# armboard.net
KiCad netlist of a schematic drawn in EAGLE
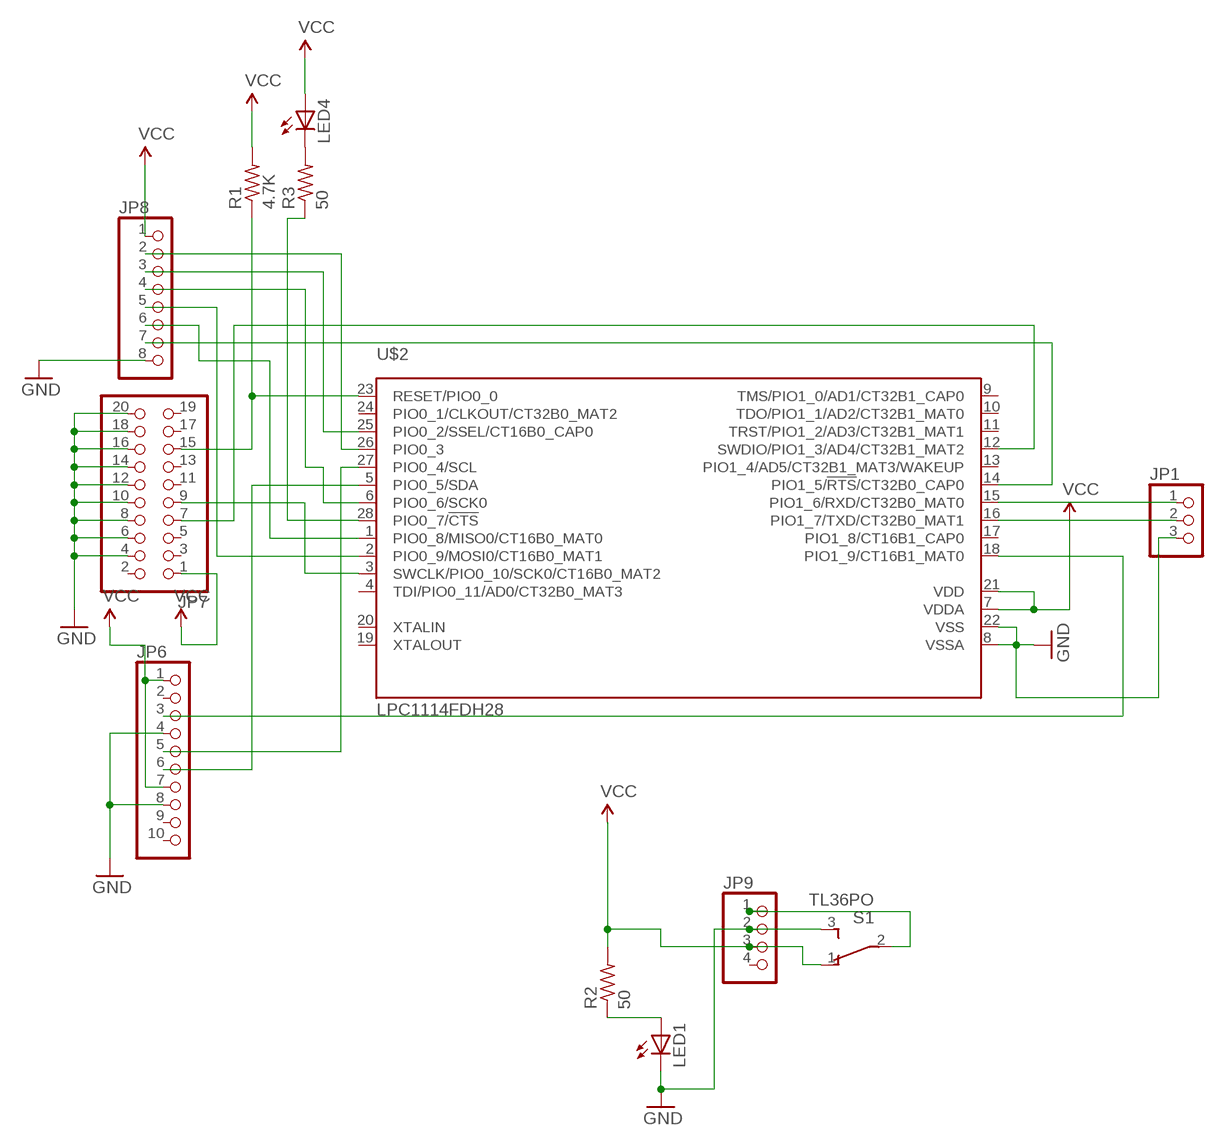
[diagram p0: schematic, sheet 1]

(export (version "E")
  (design (tool "Eeschema 10.0.6"))
  (components
    (comp (ref "JP1")
      (value "PINHD-1X3")
      (footprint "eagle-import:1X03")
      (libsource (lib "eagle-import") (part "PINHD-1X3"))
    )
    (comp (ref "JP6")
      (value "PINHD-1X10")
      (footprint "eagle-import:1X10")
      (libsource (lib "eagle-import") (part "PINHD-1X10"))
    )
    (comp (ref "JP7")
      (value "PINHD-2X10")
      (footprint "eagle-import:2X10")
      (libsource (lib "eagle-import") (part "PINHD-2X10"))
    )
    (comp (ref "JP8")
      (value "PINHD-1X8")
      (footprint "eagle-import:1X08")
      (libsource (lib "eagle-import") (part "PINHD-1X8"))
    )
    (comp (ref "JP9")
      (value "PINHD-1X4")
      (footprint "eagle-import:1X04")
      (libsource (lib "eagle-import") (part "PINHD-1X4"))
    )
    (comp (ref "LED1")
      (value "LED5MM")
      (footprint "eagle-import:LED5MM")
      (libsource (lib "eagle-import") (part "LED5MM"))
    )
    (comp (ref "LED4")
      (value "LED5MM")
      (footprint "eagle-import:LED5MM")
      (libsource (lib "eagle-import") (part "LED5MM"))
    )
    (comp (ref "R1")
      (value "4.7K")
      (footprint "eagle-import:0207_10")
      (libsource (lib "eagle-import") (part "R-US_0207/10"))
    )
    (comp (ref "R2")
      (value "50")
      (footprint "eagle-import:0207_10")
      (libsource (lib "eagle-import") (part "R-US_0207/10"))
    )
    (comp (ref "R3")
      (value "50")
      (footprint "eagle-import:0207_10")
      (libsource (lib "eagle-import") (part "R-US_0207/10"))
    )
    (comp (ref "S1")
      (value "TL36PO")
      (footprint "eagle-import:TL3XPO")
      (libsource (lib "eagle-import") (part "TL36PO"))
    )
    (comp (ref "U$2")
      (value "LPC1114FDH28")
      (footprint "eagle-import:SOT361-1")
      (libsource (lib "eagle-import") (part "LPC1114FDH28"))
    )
  )
  (nets
    (net (code "1") (name "GND") (class "Default")
      (node (ref "JP1") (pin "3") (pinfunction "3_3") (pintype "passive"))
      (node (ref "JP6") (pin "4") (pinfunction "4_4") (pintype "passive"))
      (node (ref "JP6") (pin "8") (pinfunction "8_8") (pintype "passive"))
      (node (ref "JP7") (pin "10") (pinfunction "10_10") (pintype "passive"))
      (node (ref "JP7") (pin "12") (pinfunction "12_12") (pintype "passive"))
      (node (ref "JP7") (pin "14") (pinfunction "14_14") (pintype "passive"))
      (node (ref "JP7") (pin "16") (pinfunction "16_16") (pintype "passive"))
      (node (ref "JP7") (pin "18") (pinfunction "18_18") (pintype "passive"))
      (node (ref "JP7") (pin "20") (pinfunction "20_20") (pintype "passive"))
      (node (ref "JP7") (pin "4") (pinfunction "4_4") (pintype "passive"))
      (node (ref "JP7") (pin "6") (pinfunction "6_6") (pintype "passive"))
      (node (ref "JP7") (pin "8") (pinfunction "8_8") (pintype "passive"))
      (node (ref "JP8") (pin "8") (pinfunction "8_8") (pintype "passive"))
      (node (ref "JP9") (pin "2") (pinfunction "2_2") (pintype "passive"))
      (node (ref "LED1") (pin "K") (pinfunction "C_K") (pintype "passive"))
      (node (ref "S1") (pin "3") (pinfunction "S_3") (pintype "passive"))
      (node (ref "U$2") (pin "22") (pinfunction "VSS_22") (pintype "power_in"))
      (node (ref "U$2") (pin "8") (pinfunction "VSSA_8") (pintype "power_in"))
    )
    (net (code "2") (name "Net-(LED1-PadA)") (class "Default")
      (node (ref "LED1") (pin "A") (pinfunction "A_A") (pintype "passive"))
      (node (ref "R2") (pin "1") (pinfunction "1_1") (pintype "passive"))
    )
    (net (code "3") (name "Net-(LED4-C)") (class "Default")
      (node (ref "LED4") (pin "K") (pinfunction "C_K") (pintype "passive"))
      (node (ref "R3") (pin "2") (pinfunction "2_2") (pintype "passive"))
    )
    (net (code "4") (name "Net-(S1-P)") (class "Default")
      (node (ref "JP9") (pin "1") (pinfunction "1_1") (pintype "passive"))
      (node (ref "S1") (pin "2") (pinfunction "P_2") (pintype "passive"))
    )
    (net (code "5") (name "Net-(U$2-PIO0_2{slash}SSEL{slash}CT16B0_CAP0)") (class "Default")
      (node (ref "JP8") (pin "3") (pinfunction "3_3") (pintype "passive"))
      (node (ref "U$2") (pin "25") (pinfunction "PIO0_2/SSEL/CT16B0_CAP0_25") (pintype "bidirectional"))
    )
    (net (code "6") (name "Net-(U$2-PIO0_3)") (class "Default")
      (node (ref "JP8") (pin "2") (pinfunction "2_2") (pintype "passive"))
      (node (ref "U$2") (pin "26") (pinfunction "PIO0_3_26") (pintype "bidirectional"))
    )
    (net (code "7") (name "Net-(U$2-PIO0_4{slash}SCL)") (class "Default")
      (node (ref "JP6") (pin "5") (pinfunction "5_5") (pintype "passive"))
      (node (ref "U$2") (pin "27") (pinfunction "PIO0_4/SCL_27") (pintype "bidirectional"))
    )
    (net (code "8") (name "Net-(U$2-PIO0_5{slash}SDA)") (class "Default")
      (node (ref "JP6") (pin "6") (pinfunction "6_6") (pintype "passive"))
      (node (ref "U$2") (pin "5") (pinfunction "PIO0_5/SDA_5") (pintype "bidirectional"))
    )
    (net (code "9") (name "Net-(U$2-PIO0_6{slash}SCK0)") (class "Default")
      (node (ref "JP8") (pin "4") (pinfunction "4_4") (pintype "passive"))
      (node (ref "U$2") (pin "6") (pinfunction "PIO0_6/SCK0_6") (pintype "bidirectional"))
    )
    (net (code "10") (name "Net-(U$2-PIO0_7{slash}~{CTS})") (class "Default")
      (node (ref "R3") (pin "1") (pinfunction "1_1") (pintype "passive"))
      (node (ref "U$2") (pin "28") (pinfunction "PIO0_7/~{CTS}_28") (pintype "bidirectional"))
    )
    (net (code "11") (name "Net-(U$2-PIO0_8{slash}MISO0{slash}CT16B0_MAT0)") (class "Default")
      (node (ref "JP8") (pin "6") (pinfunction "6_6") (pintype "passive"))
      (node (ref "U$2") (pin "1") (pinfunction "PIO0_8/MISO0/CT16B0_MAT0_1") (pintype "bidirectional"))
    )
    (net (code "12") (name "Net-(U$2-PIO0_9{slash}MOSI0{slash}CT16B0_MAT1)") (class "Default")
      (node (ref "JP8") (pin "5") (pinfunction "5_5") (pintype "passive"))
      (node (ref "U$2") (pin "2") (pinfunction "PIO0_9/MOSI0/CT16B0_MAT1_2") (pintype "bidirectional"))
    )
    (net (code "13") (name "Net-(U$2-PIO1_5{slash}~{RTS}{slash}CT32B0_CAP0)") (class "Default")
      (node (ref "JP8") (pin "7") (pinfunction "7_7") (pintype "passive"))
      (node (ref "U$2") (pin "14") (pinfunction "PIO1_5/~{RTS}/CT32B0_CAP0_14") (pintype "bidirectional"))
    )
    (net (code "14") (name "Net-(U$2-PIO1_6{slash}RXD{slash}CT32B0_MAT0)") (class "Default")
      (node (ref "JP1") (pin "1") (pinfunction "1_1") (pintype "passive"))
      (node (ref "U$2") (pin "15") (pinfunction "PIO1_6/RXD/CT32B0_MAT0_15") (pintype "bidirectional"))
    )
    (net (code "15") (name "Net-(U$2-PIO1_7{slash}TXD{slash}CT32B0_MAT1)") (class "Default")
      (node (ref "JP1") (pin "2") (pinfunction "2_2") (pintype "passive"))
      (node (ref "U$2") (pin "16") (pinfunction "PIO1_7/TXD/CT32B0_MAT1_16") (pintype "bidirectional"))
    )
    (net (code "16") (name "Net-(U$2-PIO1_9{slash}CT16B1_MAT0)") (class "Default")
      (node (ref "JP6") (pin "3") (pinfunction "3_3") (pintype "passive"))
      (node (ref "U$2") (pin "18") (pinfunction "PIO1_9/CT16B1_MAT0_18") (pintype "bidirectional"))
    )
    (net (code "17") (name "Net-(U$2-RESET{slash}PIO0_0)") (class "Default")
      (node (ref "JP7") (pin "15") (pinfunction "15_15") (pintype "passive"))
      (node (ref "R1") (pin "1") (pinfunction "1_1") (pintype "passive"))
      (node (ref "U$2") (pin "23") (pinfunction "RESET/PIO0_0_23") (pintype "bidirectional"))
    )
    (net (code "18") (name "Net-(U$2-SWCLK{slash}PIO0_10{slash}SCK0{slash}CT16B0_MAT2)") (class "Default")
      (node (ref "JP7") (pin "9") (pinfunction "9_9") (pintype "passive"))
      (node (ref "U$2") (pin "3") (pinfunction "SWCLK/PIO0_10/SCK0/CT16B0_MAT2_3") (pintype "bidirectional"))
    )
    (net (code "19") (name "Net-(U$2-SWDIO{slash}PIO1_3{slash}AD4{slash}CT32B1_MAT2)") (class "Default")
      (node (ref "JP7") (pin "7") (pinfunction "7_7") (pintype "passive"))
      (node (ref "U$2") (pin "12") (pinfunction "SWDIO/PIO1_3/AD4/CT32B1_MAT2_12") (pintype "bidirectional"))
    )
    (net (code "20") (name "VCC") (class "Default")
      (node (ref "JP6") (pin "1") (pinfunction "1_1") (pintype "passive"))
      (node (ref "JP6") (pin "7") (pinfunction "7_7") (pintype "passive"))
      (node (ref "JP7") (pin "1") (pinfunction "1_1") (pintype "passive"))
      (node (ref "JP8") (pin "1") (pinfunction "1_1") (pintype "passive"))
      (node (ref "JP9") (pin "3") (pinfunction "3_3") (pintype "passive"))
      (node (ref "LED4") (pin "A") (pinfunction "A_A") (pintype "passive"))
      (node (ref "R1") (pin "2") (pinfunction "2_2") (pintype "passive"))
      (node (ref "R2") (pin "2") (pinfunction "2_2") (pintype "passive"))
      (node (ref "S1") (pin "1") (pinfunction "O_1") (pintype "passive"))
      (node (ref "U$2") (pin "21") (pinfunction "VDD_21") (pintype "power_in"))
      (node (ref "U$2") (pin "7") (pinfunction "VDDA_7") (pintype "power_in"))
    )
    (net (code "21") (name "unconnected-(JP6-Pad2)") (class "Default")
      (node (ref "JP6") (pin "2") (pinfunction "2_2") (pintype "passive"))
    )
    (net (code "22") (name "unconnected-(JP6-Pad9)") (class "Default")
      (node (ref "JP6") (pin "9") (pinfunction "9_9") (pintype "passive"))
    )
    (net (code "23") (name "unconnected-(JP6-Pad10)") (class "Default")
      (node (ref "JP6") (pin "10") (pinfunction "10_10") (pintype "passive"))
    )
    (net (code "24") (name "unconnected-(JP7-Pad2)") (class "Default")
      (node (ref "JP7") (pin "2") (pinfunction "2_2") (pintype "passive"))
    )
    (net (code "25") (name "unconnected-(JP7-Pad3)") (class "Default")
      (node (ref "JP7") (pin "3") (pinfunction "3_3") (pintype "passive"))
    )
    (net (code "26") (name "unconnected-(JP7-Pad5)") (class "Default")
      (node (ref "JP7") (pin "5") (pinfunction "5_5") (pintype "passive"))
    )
    (net (code "27") (name "unconnected-(JP7-Pad11)") (class "Default")
      (node (ref "JP7") (pin "11") (pinfunction "11_11") (pintype "passive"))
    )
    (net (code "28") (name "unconnected-(JP7-Pad13)") (class "Default")
      (node (ref "JP7") (pin "13") (pinfunction "13_13") (pintype "passive"))
    )
    (net (code "29") (name "unconnected-(JP7-Pad17)") (class "Default")
      (node (ref "JP7") (pin "17") (pinfunction "17_17") (pintype "passive"))
    )
    (net (code "30") (name "unconnected-(JP7-Pad19)") (class "Default")
      (node (ref "JP7") (pin "19") (pinfunction "19_19") (pintype "passive"))
    )
    (net (code "31") (name "unconnected-(JP9-Pad4)") (class "Default")
      (node (ref "JP9") (pin "4") (pinfunction "4_4") (pintype "passive"))
    )
    (net (code "32") (name "unconnected-(U$2-PIO0_1{slash}CLKOUT{slash}CT32B0_MAT2-Pad24)") (class "Default")
      (node (ref "U$2") (pin "24") (pinfunction "PIO0_1/CLKOUT/CT32B0_MAT2_24") (pintype "bidirectional"))
    )
    (net (code "33") (name "unconnected-(U$2-PIO1_4{slash}AD5{slash}CT32B1_MAT3{slash}WAKEUP-Pad13)") (class "Default")
      (node (ref "U$2") (pin "13") (pinfunction "PIO1_4/AD5/CT32B1_MAT3/WAKEUP_13") (pintype "bidirectional"))
    )
    (net (code "34") (name "unconnected-(U$2-PIO1_8{slash}CT16B1_CAP0-Pad17)") (class "Default")
      (node (ref "U$2") (pin "17") (pinfunction "PIO1_8/CT16B1_CAP0_17") (pintype "bidirectional"))
    )
    (net (code "35") (name "unconnected-(U$2-TDI{slash}PIO0_11{slash}AD0{slash}CT32B0_MAT3-Pad4)") (class "Default")
      (node (ref "U$2") (pin "4") (pinfunction "TDI/PIO0_11/AD0/CT32B0_MAT3_4") (pintype "bidirectional"))
    )
    (net (code "36") (name "unconnected-(U$2-TDO{slash}PIO1_1{slash}AD2{slash}CT32B1_MAT0-Pad10)") (class "Default")
      (node (ref "U$2") (pin "10") (pinfunction "TDO/PIO1_1/AD2/CT32B1_MAT0_10") (pintype "bidirectional"))
    )
    (net (code "37") (name "unconnected-(U$2-TMS{slash}PIO1_0{slash}AD1{slash}CT32B1_CAP0-Pad9)") (class "Default")
      (node (ref "U$2") (pin "9") (pinfunction "TMS/PIO1_0/AD1/CT32B1_CAP0_9") (pintype "bidirectional"))
    )
    (net (code "38") (name "unconnected-(U$2-TRST{slash}PIO1_2{slash}AD3{slash}CT32B1_MAT1-Pad11)") (class "Default")
      (node (ref "U$2") (pin "11") (pinfunction "TRST/PIO1_2/AD3/CT32B1_MAT1_11") (pintype "bidirectional"))
    )
    (net (code "39") (name "unconnected-(U$2-XTALIN-Pad20)") (class "Default")
      (node (ref "U$2") (pin "20") (pinfunction "XTALIN_20") (pintype "input"))
    )
    (net (code "40") (name "unconnected-(U$2-XTALOUT-Pad19)") (class "Default")
      (node (ref "U$2") (pin "19") (pinfunction "XTALOUT_19") (pintype "output"))
    )
  )
)
